# SPTSquidBoard.net
KiCad netlist of a schematic drawn in Altium Designer
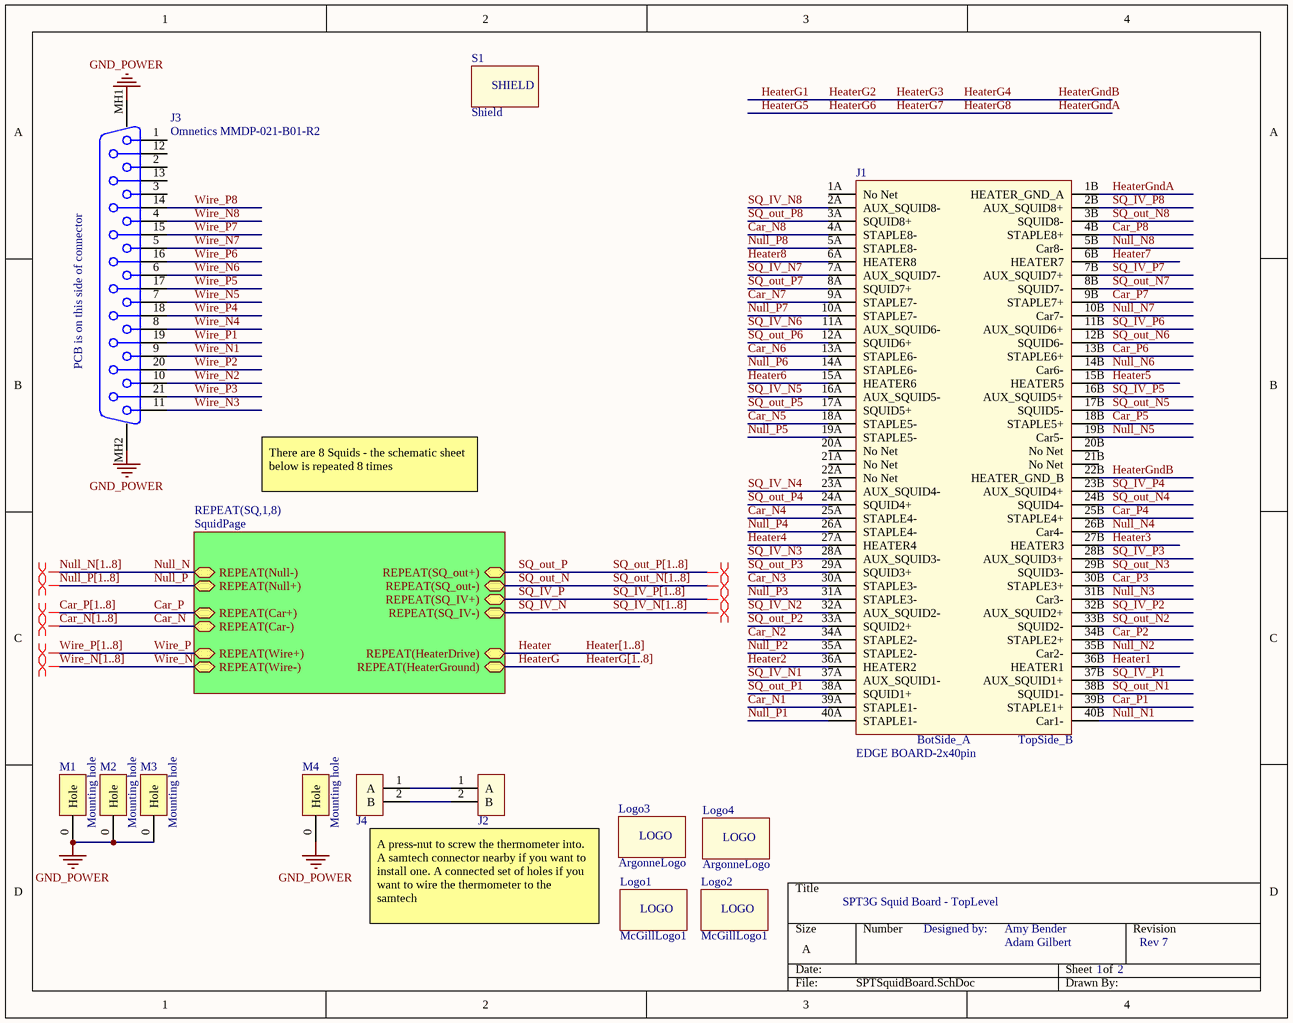
[diagram p0: SPTSquidBoard.SchDoc]

(export (version "E")
  (design (tool "Eeschema 10.0.6"))
  (components
    (comp (ref "J1")
      (value "EDGE BOARD-2x40pin")
      (description "Edge connector")
      (libsource (lib "SPT3G_LCBoard") (part "EDGE BOARD-2x40pin"))
    )
    (comp (ref "J2")
      (value "TempSenseWireConnection")
      (footprint "TempSenseWireCons")
      (libsource (lib "") (part "TempSenseCon_1"))
    )
    (comp (ref "J3")
      (value "Omnetics MMDP-021-B01-R2")
      (footprint "MMDP-021-B02-R2")
      (description "OmneticsMicroD21")
      (libsource (lib "SPT3G_LCBoard") (part "OmneticsMicroD21"))
    )
    (comp (ref "J4")
      (value "TempSenseWireConnection")
      (footprint "TempSenseWireCons")
      (libsource (lib "SPT3G_LCBoard") (part "TempSenseCon"))
    )
    (comp (ref "Logo1")
      (value "McGillLogo1")
      (footprint "McGillLogo1")
      (libsource (lib "SPT3G_LCBoard") (part "Logo"))
    )
    (comp (ref "Logo2")
      (value "McGillLogo1")
      (footprint "McGillLogo1")
      (libsource (lib "SPT3G_LCBoard") (part "Logo"))
    )
    (comp (ref "Logo3")
      (value "ArgonneLogo")
      (footprint "ArgonneLogo")
      (libsource (lib "SPT3G_AdapterBoard") (part "Logo"))
    )
    (comp (ref "Logo4")
      (value "ArgonneLogo")
      (footprint "ArgonneLogo")
      (libsource (lib "SPT3G_AdapterBoard") (part "Logo"))
    )
    (comp (ref "M1")
      (value "Mounting hole")
      (footprint "MountingHoleSquidBoard")
      (libsource (lib "SPT3G_LCBoard") (part "SquidBoardMountingHole"))
    )
    (comp (ref "M2")
      (value "Mounting hole")
      (footprint "MountingHoleSquidBoard")
      (libsource (lib "SPT3G_LCBoard") (part "SquidBoardMountingHole"))
    )
    (comp (ref "M3")
      (value "Mounting hole")
      (footprint "MountingHoleSquidBoard")
      (libsource (lib "SPT3G_LCBoard") (part "SquidBoardMountingHole"))
    )
    (comp (ref "M4")
      (value "Mounting hole")
      (footprint "MountingHoleSquidBoard")
      (libsource (lib "SPT3G_LCBoard") (part "SquidBoardMountingHole"))
    )
    (comp (ref "S1") (value "Shield") (footprint "Shield") (libsource (lib "SPT3G_LCBoard") (part "Shield")))
  )
  (nets
    (net (code "2") (name "/Car_N1") (class "Default")
      (node (ref "J1") (pin "39A") (pinfunction "STAPLE1-_39A") (pintype "passive"))
    )
    (net (code "3") (name "/Car_N2") (class "Default")
      (node (ref "J1") (pin "34A") (pinfunction "STAPLE2-_34A") (pintype "passive"))
    )
    (net (code "4") (name "/Car_N3") (class "Default")
      (node (ref "J1") (pin "30A") (pinfunction "STAPLE3-_30A") (pintype "passive"))
    )
    (net (code "5") (name "/Car_N4") (class "Default")
      (node (ref "J1") (pin "25A") (pinfunction "STAPLE4-_25A") (pintype "passive"))
    )
    (net (code "6") (name "/Car_N5") (class "Default")
      (node (ref "J1") (pin "18A") (pinfunction "STAPLE5-_18A") (pintype "passive"))
    )
    (net (code "7") (name "/Car_N6") (class "Default")
      (node (ref "J1") (pin "13A") (pinfunction "STAPLE6-_13A") (pintype "passive"))
    )
    (net (code "8") (name "/Car_N7") (class "Default")
      (node (ref "J1") (pin "9A") (pinfunction "STAPLE7-_9A") (pintype "passive"))
    )
    (net (code "9") (name "/Car_N8") (class "Default")
      (node (ref "J1") (pin "4A") (pinfunction "STAPLE8-_4A") (pintype "passive"))
    )
    (net (code "12") (name "/Car_P1") (class "Default")
      (node (ref "J1") (pin "39B") (pinfunction "STAPLE1+_39B") (pintype "passive"))
    )
    (net (code "13") (name "/Car_P2") (class "Default")
      (node (ref "J1") (pin "34B") (pinfunction "STAPLE2+_34B") (pintype "passive"))
    )
    (net (code "14") (name "/Car_P3") (class "Default")
      (node (ref "J1") (pin "30B") (pinfunction "STAPLE3+_30B") (pintype "passive"))
    )
    (net (code "15") (name "/Car_P4") (class "Default")
      (node (ref "J1") (pin "25B") (pinfunction "STAPLE4+_25B") (pintype "passive"))
    )
    (net (code "16") (name "/Car_P5") (class "Default")
      (node (ref "J1") (pin "18B") (pinfunction "STAPLE5+_18B") (pintype "passive"))
    )
    (net (code "17") (name "/Car_P6") (class "Default")
      (node (ref "J1") (pin "13B") (pinfunction "STAPLE6+_13B") (pintype "passive"))
    )
    (net (code "18") (name "/Car_P7") (class "Default")
      (node (ref "J1") (pin "9B") (pinfunction "STAPLE7+_9B") (pintype "passive"))
    )
    (net (code "19") (name "/Car_P8") (class "Default")
      (node (ref "J1") (pin "4B") (pinfunction "STAPLE8+_4B") (pintype "passive"))
    )
    (net (code "22") (name "/Heater1") (class "Default")
      (node (ref "J1") (pin "36B") (pinfunction "HEATER1_36B") (pintype "passive"))
    )
    (net (code "23") (name "/Heater2") (class "Default")
      (node (ref "J1") (pin "36A") (pinfunction "HEATER2_36A") (pintype "passive"))
    )
    (net (code "24") (name "/Heater3") (class "Default")
      (node (ref "J1") (pin "27B") (pinfunction "HEATER3_27B") (pintype "passive"))
    )
    (net (code "25") (name "/Heater4") (class "Default")
      (node (ref "J1") (pin "27A") (pinfunction "HEATER4_27A") (pintype "passive"))
    )
    (net (code "26") (name "/Heater5") (class "Default")
      (node (ref "J1") (pin "15B") (pinfunction "HEATER5_15B") (pintype "passive"))
    )
    (net (code "27") (name "/Heater6") (class "Default")
      (node (ref "J1") (pin "15A") (pinfunction "HEATER6_15A") (pintype "passive"))
    )
    (net (code "28") (name "/Heater7") (class "Default")
      (node (ref "J1") (pin "6B") (pinfunction "HEATER7_6B") (pintype "passive"))
    )
    (net (code "29") (name "/Heater8") (class "Default")
      (node (ref "J1") (pin "6A") (pinfunction "HEATER8_6A") (pintype "passive"))
    )
    (net (code "31") (name "/HeaterG4") (class "Default")
      (node (ref "J1") (pin "22B") (pinfunction "HEATER_GND_B_22B") (pintype "passive"))
    )
    (net (code "32") (name "/HeaterG8") (class "Default")
      (node (ref "J1") (pin "1B") (pinfunction "HEATER_GND_A_1B") (pintype "passive"))
    )
    (net (code "36") (name "/Null_N1") (class "Default")
      (node (ref "J1") (pin "40B") (pinfunction "Car1-_40B") (pintype "passive"))
    )
    (net (code "37") (name "/Null_N2") (class "Default")
      (node (ref "J1") (pin "35B") (pinfunction "Car2-_35B") (pintype "passive"))
    )
    (net (code "38") (name "/Null_N3") (class "Default")
      (node (ref "J1") (pin "31B") (pinfunction "Car3-_31B") (pintype "passive"))
    )
    (net (code "39") (name "/Null_N4") (class "Default")
      (node (ref "J1") (pin "26B") (pinfunction "Car4-_26B") (pintype "passive"))
    )
    (net (code "40") (name "/Null_N5") (class "Default")
      (node (ref "J1") (pin "19B") (pinfunction "Car5-_19B") (pintype "passive"))
    )
    (net (code "41") (name "/Null_N6") (class "Default")
      (node (ref "J1") (pin "14B") (pinfunction "Car6-_14B") (pintype "passive"))
    )
    (net (code "42") (name "/Null_N7") (class "Default")
      (node (ref "J1") (pin "10B") (pinfunction "Car7-_10B") (pintype "passive"))
    )
    (net (code "43") (name "/Null_N8") (class "Default")
      (node (ref "J1") (pin "5B") (pinfunction "Car8-_5B") (pintype "passive"))
    )
    (net (code "46") (name "/Null_P1") (class "Default")
      (node (ref "J1") (pin "40A") (pinfunction "STAPLE1-_40A") (pintype "passive"))
    )
    (net (code "47") (name "/Null_P2") (class "Default")
      (node (ref "J1") (pin "35A") (pinfunction "STAPLE2-_35A") (pintype "passive"))
    )
    (net (code "48") (name "/Null_P3") (class "Default")
      (node (ref "J1") (pin "31A") (pinfunction "STAPLE3-_31A") (pintype "passive"))
    )
    (net (code "49") (name "/Null_P4") (class "Default")
      (node (ref "J1") (pin "26A") (pinfunction "STAPLE4-_26A") (pintype "passive"))
    )
    (net (code "50") (name "/Null_P5") (class "Default")
      (node (ref "J1") (pin "19A") (pinfunction "STAPLE5-_19A") (pintype "passive"))
    )
    (net (code "51") (name "/Null_P6") (class "Default")
      (node (ref "J1") (pin "14A") (pinfunction "STAPLE6-_14A") (pintype "passive"))
    )
    (net (code "52") (name "/Null_P7") (class "Default")
      (node (ref "J1") (pin "10A") (pinfunction "STAPLE7-_10A") (pintype "passive"))
    )
    (net (code "53") (name "/Null_P8") (class "Default")
      (node (ref "J1") (pin "5A") (pinfunction "STAPLE8-_5A") (pintype "passive"))
    )
    (net (code "56") (name "/SQ_IV_N1") (class "Default")
      (node (ref "J1") (pin "37A") (pinfunction "AUX_SQUID1-_37A") (pintype "passive"))
    )
    (net (code "57") (name "/SQ_IV_N2") (class "Default")
      (node (ref "J1") (pin "32A") (pinfunction "AUX_SQUID2-_32A") (pintype "passive"))
    )
    (net (code "58") (name "/SQ_IV_N3") (class "Default")
      (node (ref "J1") (pin "28A") (pinfunction "AUX_SQUID3-_28A") (pintype "passive"))
    )
    (net (code "59") (name "/SQ_IV_N4") (class "Default")
      (node (ref "J1") (pin "23A") (pinfunction "AUX_SQUID4-_23A") (pintype "passive"))
    )
    (net (code "60") (name "/SQ_IV_N5") (class "Default")
      (node (ref "J1") (pin "16A") (pinfunction "AUX_SQUID5-_16A") (pintype "passive"))
    )
    (net (code "61") (name "/SQ_IV_N6") (class "Default")
      (node (ref "J1") (pin "11A") (pinfunction "AUX_SQUID6-_11A") (pintype "passive"))
    )
    (net (code "62") (name "/SQ_IV_N7") (class "Default")
      (node (ref "J1") (pin "7A") (pinfunction "AUX_SQUID7-_7A") (pintype "passive"))
    )
    (net (code "63") (name "/SQ_IV_N8") (class "Default")
      (node (ref "J1") (pin "2A") (pinfunction "AUX_SQUID8-_2A") (pintype "passive"))
    )
    (net (code "66") (name "/SQ_IV_P1") (class "Default")
      (node (ref "J1") (pin "37B") (pinfunction "AUX_SQUID1+_37B") (pintype "passive"))
    )
    (net (code "67") (name "/SQ_IV_P2") (class "Default")
      (node (ref "J1") (pin "32B") (pinfunction "AUX_SQUID2+_32B") (pintype "passive"))
    )
    (net (code "68") (name "/SQ_IV_P3") (class "Default")
      (node (ref "J1") (pin "28B") (pinfunction "AUX_SQUID3+_28B") (pintype "passive"))
    )
    (net (code "69") (name "/SQ_IV_P4") (class "Default")
      (node (ref "J1") (pin "23B") (pinfunction "AUX_SQUID4+_23B") (pintype "passive"))
    )
    (net (code "70") (name "/SQ_IV_P5") (class "Default")
      (node (ref "J1") (pin "16B") (pinfunction "AUX_SQUID5+_16B") (pintype "passive"))
    )
    (net (code "71") (name "/SQ_IV_P6") (class "Default")
      (node (ref "J1") (pin "11B") (pinfunction "AUX_SQUID6+_11B") (pintype "passive"))
    )
    (net (code "72") (name "/SQ_IV_P7") (class "Default")
      (node (ref "J1") (pin "7B") (pinfunction "AUX_SQUID7+_7B") (pintype "passive"))
    )
    (net (code "73") (name "/SQ_IV_P8") (class "Default")
      (node (ref "J1") (pin "2B") (pinfunction "AUX_SQUID8+_2B") (pintype "passive"))
    )
    (net (code "76") (name "/SQ_out_N1") (class "Default")
      (node (ref "J1") (pin "38B") (pinfunction "SQUID1-_38B") (pintype "passive"))
    )
    (net (code "77") (name "/SQ_out_N2") (class "Default")
      (node (ref "J1") (pin "33B") (pinfunction "SQUID2-_33B") (pintype "passive"))
    )
    (net (code "78") (name "/SQ_out_N3") (class "Default")
      (node (ref "J1") (pin "29B") (pinfunction "SQUID3-_29B") (pintype "passive"))
    )
    (net (code "79") (name "/SQ_out_N4") (class "Default")
      (node (ref "J1") (pin "24B") (pinfunction "SQUID4-_24B") (pintype "passive"))
    )
    (net (code "80") (name "/SQ_out_N5") (class "Default")
      (node (ref "J1") (pin "17B") (pinfunction "SQUID5-_17B") (pintype "passive"))
    )
    (net (code "81") (name "/SQ_out_N6") (class "Default")
      (node (ref "J1") (pin "12B") (pinfunction "SQUID6-_12B") (pintype "passive"))
    )
    (net (code "82") (name "/SQ_out_N7") (class "Default")
      (node (ref "J1") (pin "8B") (pinfunction "SQUID7-_8B") (pintype "passive"))
    )
    (net (code "83") (name "/SQ_out_N8") (class "Default")
      (node (ref "J1") (pin "3B") (pinfunction "SQUID8-_3B") (pintype "passive"))
    )
    (net (code "86") (name "/SQ_out_P1") (class "Default")
      (node (ref "J1") (pin "38A") (pinfunction "SQUID1+_38A") (pintype "passive"))
    )
    (net (code "87") (name "/SQ_out_P2") (class "Default")
      (node (ref "J1") (pin "33A") (pinfunction "SQUID2+_33A") (pintype "passive"))
    )
    (net (code "88") (name "/SQ_out_P3") (class "Default")
      (node (ref "J1") (pin "29A") (pinfunction "SQUID3+_29A") (pintype "passive"))
    )
    (net (code "89") (name "/SQ_out_P4") (class "Default")
      (node (ref "J1") (pin "24A") (pinfunction "SQUID4+_24A") (pintype "passive"))
    )
    (net (code "90") (name "/SQ_out_P5") (class "Default")
      (node (ref "J1") (pin "17A") (pinfunction "SQUID5+_17A") (pintype "passive"))
    )
    (net (code "91") (name "/SQ_out_P6") (class "Default")
      (node (ref "J1") (pin "12A") (pinfunction "SQUID6+_12A") (pintype "passive"))
    )
    (net (code "92") (name "/SQ_out_P7") (class "Default")
      (node (ref "J1") (pin "8A") (pinfunction "SQUID7+_8A") (pintype "passive"))
    )
    (net (code "93") (name "/SQ_out_P8") (class "Default")
      (node (ref "J1") (pin "3A") (pinfunction "SQUID8+_3A") (pintype "passive"))
    )
    (net (code "96") (name "/Wire_N1") (class "Default")
      (node (ref "J3") (pin "9") (pinfunction "9_9") (pintype "passive"))
    )
    (net (code "97") (name "/Wire_N2") (class "Default")
      (node (ref "J3") (pin "10") (pinfunction "10_10") (pintype "passive"))
    )
    (net (code "98") (name "/Wire_N3") (class "Default")
      (node (ref "J3") (pin "11") (pinfunction "11_11") (pintype "passive"))
    )
    (net (code "99") (name "/Wire_N4") (class "Default")
      (node (ref "J3") (pin "8") (pinfunction "8_8") (pintype "passive"))
    )
    (net (code "100") (name "/Wire_N5") (class "Default")
      (node (ref "J3") (pin "7") (pinfunction "7_7") (pintype "passive"))
    )
    (net (code "101") (name "/Wire_N6") (class "Default")
      (node (ref "J3") (pin "6") (pinfunction "6_6") (pintype "passive"))
    )
    (net (code "102") (name "/Wire_N7") (class "Default")
      (node (ref "J3") (pin "5") (pinfunction "5_5") (pintype "passive"))
    )
    (net (code "103") (name "/Wire_N8") (class "Default")
      (node (ref "J3") (pin "4") (pinfunction "4_4") (pintype "passive"))
    )
    (net (code "106") (name "/Wire_P1") (class "Default")
      (node (ref "J3") (pin "19") (pinfunction "19_19") (pintype "passive"))
    )
    (net (code "107") (name "/Wire_P2") (class "Default")
      (node (ref "J3") (pin "20") (pinfunction "20_20") (pintype "passive"))
    )
    (net (code "108") (name "/Wire_P3") (class "Default")
      (node (ref "J3") (pin "21") (pinfunction "21_21") (pintype "passive"))
    )
    (net (code "109") (name "/Wire_P4") (class "Default")
      (node (ref "J3") (pin "18") (pinfunction "18_18") (pintype "passive"))
    )
    (net (code "110") (name "/Wire_P5") (class "Default")
      (node (ref "J3") (pin "17") (pinfunction "17_17") (pintype "passive"))
    )
    (net (code "111") (name "/Wire_P6") (class "Default")
      (node (ref "J3") (pin "16") (pinfunction "16_16") (pintype "passive"))
    )
    (net (code "112") (name "/Wire_P7") (class "Default")
      (node (ref "J3") (pin "15") (pinfunction "15_15") (pintype "passive"))
    )
    (net (code "113") (name "/Wire_P8") (class "Default")
      (node (ref "J3") (pin "14") (pinfunction "14_14") (pintype "passive"))
    )
    (net (code "115") (name "GND_POWER") (class "Default")
      (node (ref "J3") (pin "MH1") (pinfunction "MH1_MH1") (pintype "passive"))
      (node (ref "J3") (pin "MH2") (pinfunction "MH2_MH2") (pintype "passive"))
      (node (ref "M1") (pin "0") (pinfunction "Hole_0") (pintype "passive"))
      (node (ref "M2") (pin "0") (pinfunction "Hole_0") (pintype "passive"))
      (node (ref "M3") (pin "0") (pinfunction "Hole_0") (pintype "passive"))
      (node (ref "M4") (pin "0") (pinfunction "Hole_0") (pintype "passive"))
    )
    (net (code "116") (name "Net-(J2-A)") (class "Default")
      (node (ref "J2") (pin "1") (pinfunction "A_1") (pintype "passive"))
      (node (ref "J4") (pin "1") (pinfunction "A_1") (pintype "passive"))
    )
    (net (code "117") (name "Net-(J2-B)") (class "Default")
      (node (ref "J2") (pin "2") (pinfunction "B_2") (pintype "passive"))
      (node (ref "J4") (pin "2") (pinfunction "B_2") (pintype "passive"))
    )
    (net (code "118") (name "unconnected-(J1-No_Net-Pad1A)") (class "Default")
      (node (ref "J1") (pin "1A") (pinfunction "No_Net_1A") (pintype "passive"))
    )
    (net (code "119") (name "unconnected-(J1-No_Net-Pad20A)") (class "Default")
      (node (ref "J1") (pin "20A") (pinfunction "No_Net_20A") (pintype "passive"))
    )
    (net (code "120") (name "unconnected-(J1-No_Net-Pad20B)") (class "Default")
      (node (ref "J1") (pin "20B") (pinfunction "No_Net_20B") (pintype "passive"))
    )
    (net (code "121") (name "unconnected-(J1-No_Net-Pad21A)") (class "Default")
      (node (ref "J1") (pin "21A") (pinfunction "No_Net_21A") (pintype "passive"))
    )
    (net (code "122") (name "unconnected-(J1-No_Net-Pad21B)") (class "Default")
      (node (ref "J1") (pin "21B") (pinfunction "No_Net_21B") (pintype "passive"))
    )
    (net (code "123") (name "unconnected-(J1-No_Net-Pad22A)") (class "Default")
      (node (ref "J1") (pin "22A") (pinfunction "No_Net_22A") (pintype "passive"))
    )
    (net (code "124") (name "unconnected-(J3-Pad1)") (class "Default")
      (node (ref "J3") (pin "1") (pinfunction "1_1") (pintype "passive"))
    )
    (net (code "125") (name "unconnected-(J3-Pad2)") (class "Default")
      (node (ref "J3") (pin "2") (pinfunction "2_2") (pintype "passive"))
    )
    (net (code "126") (name "unconnected-(J3-Pad3)") (class "Default")
      (node (ref "J3") (pin "3") (pinfunction "3_3") (pintype "passive"))
    )
    (net (code "127") (name "unconnected-(J3-Pad12)") (class "Default")
      (node (ref "J3") (pin "12") (pinfunction "12_12") (pintype "passive"))
    )
    (net (code "128") (name "unconnected-(J3-Pad13)") (class "Default")
      (node (ref "J3") (pin "13") (pinfunction "13_13") (pintype "passive"))
    )
  )
)
